# nerf.net
KiCad netlist of a schematic drawn in Altium Designer
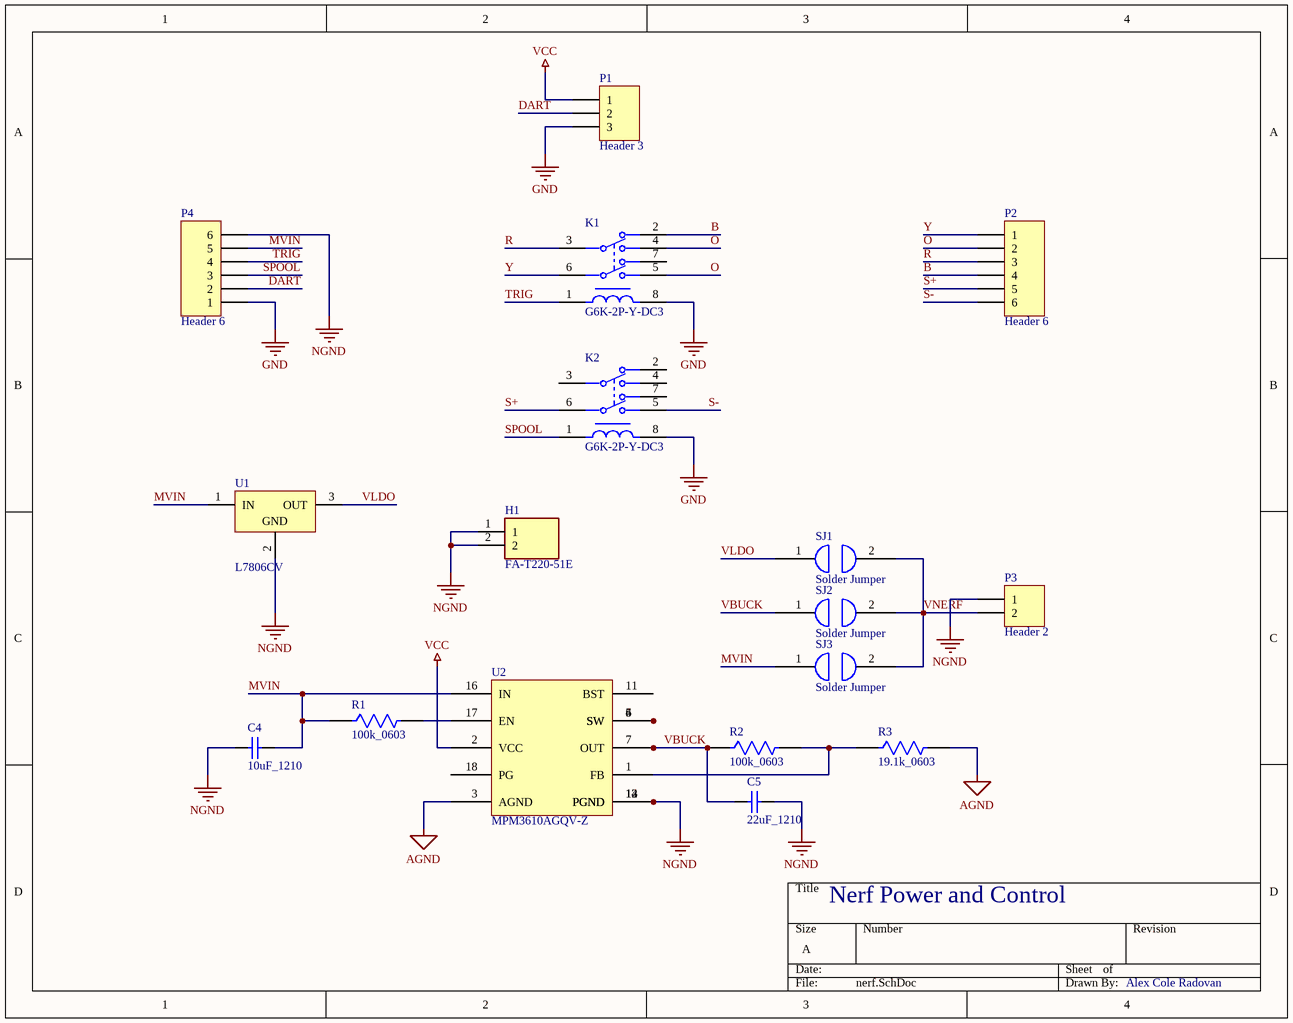
[diagram p0: nerf.SchDoc]

(export (version "E")
  (design (tool "Eeschema 10.0.6"))
  (components
    (comp (ref "C4")
      (value "10uF_1210")
      (footprint "CAPC3325X28N")
      (description "1210 Standard 10uF Ceramic Multilayer Cap")
      (fields (field (name "TOLERANCE") "10%"))
      (libsource (lib "Oases") (part "CAP"))
    )
    (comp (ref "C5")
      (value "22uF_1210")
      (footprint "CAPC3325X28N")
      (description "1210 Standard 22uF Ceramic Multilayer Cap")
      (fields (field (name "TOLERANCE") "10%"))
      (libsource (lib "Oases") (part "CAP"))
    )
    (comp (ref "H1")
      (value "FA-T220-51E")
      (footprint "SamacSys:FAT22051E")
      (description "Hardware")
      (libsource (lib "*") (part "FA-T220-51E"))
    )
    (comp (ref "K1")
      (value "G6K-2P-Y-DC3")
      (footprint "FP-G6K-2P-Y_DC3-MFG")
      (description "Relay; E-Mech; Low Signal; DPDT; Cur-Rtg 0.3/1AAC/ADC; Ctrl-V 3DC; Vol-Rtg 125/30AC/DC")
      (libsource (lib "Oases") (part "f6f6c627aadb73ad41e05903558ffa9"))
    )
    (comp (ref "K2")
      (value "G6K-2P-Y-DC3")
      (footprint "FP-G6K-2P-Y_DC3-MFG")
      (description "Relay; E-Mech; Low Signal; DPDT; Cur-Rtg 0.3/1AAC/ADC; Ctrl-V 3DC; Vol-Rtg 125/30AC/DC")
      (libsource (lib "Oases") (part "f6f6c627aadb73ad41e05903558ffa9"))
    )
    (comp (ref "P1")
      (value "Header 3")
      (footprint "HDR1X3")
      (description "Header, 3-Pin")
      (fields (field (name "PUBLISHER") "Altium Limited"))
      (libsource (lib "Miscellaneous Connectors") (part "Header 3"))
    )
    (comp (ref "P2")
      (value "Header 6")
      (footprint "HDR1X6")
      (description "Header, 6-Pin")
      (fields (field (name "PUBLISHER") "Altium Limited"))
      (libsource (lib "") (part "Header 6_1"))
    )
    (comp (ref "P3")
      (value "Header 2")
      (footprint "HDR1X2")
      (description "Header, 2-Pin")
      (fields (field (name "PUBLISHER") "Altium Limited"))
      (libsource (lib "Miscellaneous Connectors") (part "Header 2"))
    )
    (comp (ref "P4")
      (value "Header 6")
      (footprint "HDR1X6")
      (description "Header, 6-Pin")
      (fields (field (name "PUBLISHER") "Altium Limited"))
      (libsource (lib "Miscellaneous Connectors") (part "Header 6"))
    )
    (comp (ref "R1")
      (value "100k_0603")
      (footprint "RESC1608X05N")
      (description "Res Thick Film 0603 100K Ohm")
      (fields (field (name "TOLERANCE") "1%"))
      (libsource (lib "Oases") (part "RES"))
    )
    (comp (ref "R2")
      (value "100k_0603")
      (footprint "RESC1608X05N")
      (description "Res Thick Film 0603 100K Ohm")
      (fields (field (name "TOLERANCE") "1%"))
      (libsource (lib "Oases") (part "RES"))
    )
    (comp (ref "R3")
      (value "19.1k_0603")
      (footprint "RESC1608X05N")
      (description "19.1K Ohm")
      (fields (field (name "TOLERANCE") "1%"))
      (libsource (lib "Oases") (part "RES"))
    )
    (comp (ref "SJ1")
      (value "Solder Jumper")
      (footprint "SJ-Footprint")
      (description "NO Solder Jumper")
      (libsource (lib "Oases") (part "SJ-Symbol"))
    )
    (comp (ref "SJ2")
      (value "Solder Jumper")
      (footprint "SJ-Footprint")
      (description "NO Solder Jumper")
      (libsource (lib "Oases") (part "SJ-Symbol"))
    )
    (comp (ref "SJ3")
      (value "Solder Jumper")
      (footprint "SJ-Footprint")
      (description "NO Solder Jumper")
      (libsource (lib "Oases") (part "SJ-Symbol"))
    )
    (comp (ref "U1")
      (value "L7806CV")
      (footprint "TO220")
      (description "L7806 Series 1.5 A 6 V Three Terminal Voltage Regulator - TO-220")
      (fields (field (name "TOLERANCE") "5%"))
      (libsource (lib "Oases") (part "PM-REG-L4940-SIL3"))
    )
    (comp (ref "U2")
      (value "MPM3610AGQV-Z")
      (footprint "MPM3610AGQV-Z-Footprint-1")
      (description "MPM3610A Series 21 V 1.2 A Adj. SMT Synchronous Step-Down Converter - QFN-20")
      (libsource (lib "Oases") (part "MPM3610AGQV-Z"))
    )
  )
  (nets
    (net (code "1") (name "/B") (class "Default")
      (node (ref "K1") (pin "2") (pinfunction "2_2") (pintype "passive"))
      (node (ref "P2") (pin "4") (pinfunction "4_4") (pintype "passive"))
    )
    (net (code "2") (name "/DART") (class "Default")
      (node (ref "P1") (pin "2") (pinfunction "2_2") (pintype "passive"))
      (node (ref "P4") (pin "2") (pinfunction "2_2") (pintype "passive"))
    )
    (net (code "3") (name "/MVIN") (class "Default")
      (node (ref "C4") (pin "2") (pinfunction "2_2") (pintype "passive"))
      (node (ref "P4") (pin "5") (pinfunction "5_5") (pintype "passive"))
      (node (ref "R1") (pin "1") (pinfunction "1_1") (pintype "passive"))
      (node (ref "SJ3") (pin "1") (pinfunction "*_1") (pintype "passive"))
      (node (ref "U1") (pin "1") (pinfunction "IN_1") (pintype "power_in"))
      (node (ref "U2") (pin "16") (pinfunction "IN_16") (pintype "passive"))
    )
    (net (code "4") (name "/O") (class "Default")
      (node (ref "K1") (pin "4") (pinfunction "4_4") (pintype "passive"))
      (node (ref "K1") (pin "5") (pinfunction "5_5") (pintype "passive"))
      (node (ref "P2") (pin "2") (pinfunction "2_2") (pintype "passive"))
    )
    (net (code "5") (name "/R") (class "Default")
      (node (ref "K1") (pin "3") (pinfunction "3_3") (pintype "passive"))
      (node (ref "P2") (pin "3") (pinfunction "3_3") (pintype "passive"))
    )
    (net (code "6") (name "/S+") (class "Default")
      (node (ref "K2") (pin "6") (pinfunction "6_6") (pintype "passive"))
      (node (ref "P2") (pin "5") (pinfunction "5_5") (pintype "passive"))
    )
    (net (code "7") (name "/S-") (class "Default")
      (node (ref "K2") (pin "5") (pinfunction "5_5") (pintype "passive"))
      (node (ref "P2") (pin "6") (pinfunction "6_6") (pintype "passive"))
    )
    (net (code "8") (name "/SPOOL") (class "Default")
      (node (ref "K2") (pin "1") (pinfunction "1_1") (pintype "passive"))
      (node (ref "P4") (pin "3") (pinfunction "3_3") (pintype "passive"))
    )
    (net (code "9") (name "/TRIG") (class "Default")
      (node (ref "K1") (pin "1") (pinfunction "1_1") (pintype "passive"))
      (node (ref "P4") (pin "4") (pinfunction "4_4") (pintype "passive"))
    )
    (net (code "10") (name "/VBUCK") (class "Default")
      (node (ref "C5") (pin "1") (pinfunction "1_1") (pintype "passive"))
      (node (ref "R2") (pin "1") (pinfunction "1_1") (pintype "passive"))
      (node (ref "SJ2") (pin "1") (pinfunction "*_1") (pintype "passive"))
      (node (ref "U2") (pin "7") (pinfunction "OUT_7") (pintype "passive"))
      (node (ref "U2") (pin "8") (pinfunction "OUT_8") (pintype "passive"))
      (node (ref "U2") (pin "9") (pinfunction "OUT_9") (pintype "passive"))
    )
    (net (code "11") (name "/VLDO") (class "Default")
      (node (ref "SJ1") (pin "1") (pinfunction "*_1") (pintype "passive"))
      (node (ref "U1") (pin "3") (pinfunction "OUT_3") (pintype "power_in"))
    )
    (net (code "12") (name "/VNERF") (class "Default")
      (node (ref "P3") (pin "2") (pinfunction "2_2") (pintype "passive"))
      (node (ref "SJ1") (pin "2") (pinfunction "*_2") (pintype "passive"))
      (node (ref "SJ2") (pin "2") (pinfunction "*_2") (pintype "passive"))
      (node (ref "SJ3") (pin "2") (pinfunction "*_2") (pintype "passive"))
    )
    (net (code "13") (name "/Y") (class "Default")
      (node (ref "K1") (pin "6") (pinfunction "6_6") (pintype "passive"))
      (node (ref "P2") (pin "1") (pinfunction "1_1") (pintype "passive"))
    )
    (net (code "14") (name "AGND") (class "Default")
      (node (ref "R3") (pin "2") (pinfunction "2_2") (pintype "passive"))
      (node (ref "U2") (pin "3") (pinfunction "AGND_3") (pintype "passive"))
    )
    (net (code "15") (name "GND") (class "Default")
      (node (ref "K1") (pin "8") (pinfunction "8_8") (pintype "passive"))
      (node (ref "K2") (pin "8") (pinfunction "8_8") (pintype "passive"))
      (node (ref "P1") (pin "3") (pinfunction "3_3") (pintype "passive"))
      (node (ref "P4") (pin "1") (pinfunction "1_1") (pintype "passive"))
    )
    (net (code "16") (name "NGND") (class "Default")
      (node (ref "C4") (pin "1") (pinfunction "1_1") (pintype "passive"))
      (node (ref "C5") (pin "2") (pinfunction "2_2") (pintype "passive"))
      (node (ref "H1") (pin "1") (pinfunction "1_1") (pintype "passive"))
      (node (ref "H1") (pin "2") (pinfunction "2_2") (pintype "passive"))
      (node (ref "P3") (pin "1") (pinfunction "1_1") (pintype "passive"))
      (node (ref "P4") (pin "6") (pinfunction "6_6") (pintype "passive"))
      (node (ref "U1") (pin "2") (pinfunction "GND_2") (pintype "power_in"))
      (node (ref "U2") (pin "12") (pinfunction "PGND_12") (pintype "passive"))
      (node (ref "U2") (pin "13") (pinfunction "PGND_13") (pintype "passive"))
      (node (ref "U2") (pin "14") (pinfunction "PGND_14") (pintype "passive"))
    )
    (net (code "17") (name "Net-(U2-EN)") (class "Default")
      (node (ref "R1") (pin "2") (pinfunction "2_2") (pintype "passive"))
      (node (ref "U2") (pin "17") (pinfunction "EN_17") (pintype "passive"))
    )
    (net (code "18") (name "Net-(U2-FB)") (class "Default")
      (node (ref "R2") (pin "2") (pinfunction "2_2") (pintype "passive"))
      (node (ref "R3") (pin "1") (pinfunction "1_1") (pintype "passive"))
      (node (ref "U2") (pin "1") (pinfunction "FB_1") (pintype "passive"))
    )
    (net (code "19") (name "Net-(U2-SW-Pad4)") (class "Default")
      (node (ref "U2") (pin "4") (pinfunction "SW_4") (pintype "passive"))
      (node (ref "U2") (pin "5") (pinfunction "SW_5") (pintype "passive"))
      (node (ref "U2") (pin "6") (pinfunction "SW_6") (pintype "passive"))
    )
    (net (code "20") (name "VCC") (class "Default")
      (node (ref "P1") (pin "1") (pinfunction "1_1") (pintype "passive"))
      (node (ref "U2") (pin "2") (pinfunction "VCC_2") (pintype "passive"))
    )
    (net (code "21") (name "unconnected-(K1-Pad7)") (class "Default")
      (node (ref "K1") (pin "7") (pinfunction "7_7") (pintype "passive"))
    )
    (net (code "22") (name "unconnected-(K2-Pad2)") (class "Default")
      (node (ref "K2") (pin "2") (pinfunction "2_2") (pintype "passive"))
    )
    (net (code "23") (name "unconnected-(K2-Pad3)") (class "Default")
      (node (ref "K2") (pin "3") (pinfunction "3_3") (pintype "passive"))
    )
    (net (code "24") (name "unconnected-(K2-Pad4)") (class "Default")
      (node (ref "K2") (pin "4") (pinfunction "4_4") (pintype "passive"))
    )
    (net (code "25") (name "unconnected-(K2-Pad7)") (class "Default")
      (node (ref "K2") (pin "7") (pinfunction "7_7") (pintype "passive"))
    )
    (net (code "26") (name "unconnected-(U2-BST-Pad11)") (class "Default")
      (node (ref "U2") (pin "11") (pinfunction "BST_11") (pintype "passive"))
    )
    (net (code "27") (name "unconnected-(U2-PG-Pad18)") (class "Default")
      (node (ref "U2") (pin "18") (pinfunction "PG_18") (pintype "passive"))
    )
  )
)
